# cart-breakout-r2.net
KiCad netlist of a schematic drawn in EAGLE
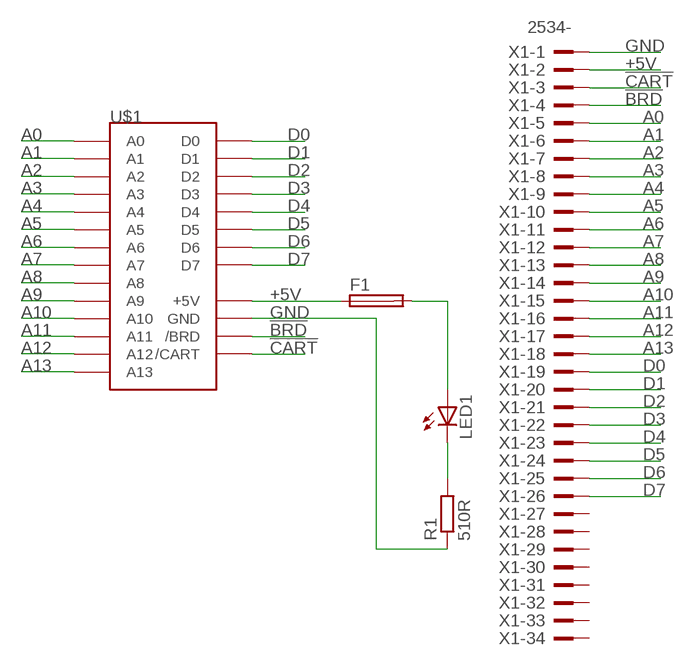
[diagram p0: schematic, sheet 1]

(export (version "E")
  (design (tool "Eeschema 10.0.6"))
  (components
    (comp (ref "F1")
      (value "TE5")
      (footprint "eagle-import:TE5")
      (libsource (lib "eagle-import") (part "TE5"))
    )
    (comp (ref "LED1")
      (value "LED5MM")
      (footprint "eagle-import:LED5MM")
      (libsource (lib "eagle-import") (part "LED5MM"))
    )
    (comp (ref "R1")
      (value "510R")
      (footprint "eagle-import:0204_7")
      (libsource (lib "eagle-import") (part "R-EU_0204/7"))
    )
    (comp (ref "U$1")
      (value "TVC-CART-EDGE+")
      (footprint "eagle-import:TVC-CART-EDGE")
      (libsource (lib "eagle-import") (part "TVC-CART-EDGE+"))
    )
    (comp (ref "X1")
      (value "2534-")
      (footprint "eagle-import:PAK100_2500-34")
      (libsource (lib "eagle-import") (part "2534-"))
    )
  )
  (nets
    (net (code "1") (name "/+5V") (class "Default")
      (node (ref "F1") (pin "1") (pinfunction "1_1") (pintype "passive"))
      (node (ref "F1") (pin "2") (pinfunction "2_2") (pintype "passive"))
      (node (ref "LED1") (pin "A") (pinfunction "A_A") (pintype "passive"))
      (node (ref "U$1") (pin "BTM10") (pinfunction "+5V_BTM10") (pintype "power_in"))
      (node (ref "U$1") (pin "BTM11") (pinfunction "+5V_BTM11") (pintype "power_in"))
      (node (ref "U$1") (pin "BTM12") (pinfunction "+5V_BTM12") (pintype "power_in"))
      (node (ref "U$1") (pin "BTM13") (pinfunction "+5V_BTM13") (pintype "power_in"))
      (node (ref "U$1") (pin "BTM14") (pinfunction "+5V_BTM14") (pintype "power_in"))
      (node (ref "U$1") (pin "BTM15") (pinfunction "+5V_BTM15") (pintype "power_in"))
      (node (ref "U$1") (pin "BTM16") (pinfunction "+5V_BTM16") (pintype "power_in"))
      (node (ref "U$1") (pin "BTM17") (pinfunction "+5V_BTM17") (pintype "power_in"))
      (node (ref "X1") (pin "2") (pinfunction "KL_2") (pintype "passive"))
    )
    (net (code "2") (name "/A0") (class "Default")
      (node (ref "U$1") (pin "TOP25") (pinfunction "A0_TOP25") (pintype "bidirectional"))
      (node (ref "X1") (pin "5") (pinfunction "KL_5") (pintype "passive"))
    )
    (net (code "3") (name "/A1") (class "Default")
      (node (ref "U$1") (pin "TOP2") (pinfunction "A1_TOP2") (pintype "bidirectional"))
      (node (ref "X1") (pin "6") (pinfunction "KL_6") (pintype "passive"))
    )
    (net (code "4") (name "/A2") (class "Default")
      (node (ref "U$1") (pin "TOP24") (pinfunction "A2_TOP24") (pintype "bidirectional"))
      (node (ref "X1") (pin "7") (pinfunction "KL_7") (pintype "passive"))
    )
    (net (code "5") (name "/A3") (class "Default")
      (node (ref "U$1") (pin "TOP1") (pinfunction "A3_TOP1") (pintype "bidirectional"))
      (node (ref "X1") (pin "8") (pinfunction "KL_8") (pintype "passive"))
    )
    (net (code "6") (name "/A4") (class "Default")
      (node (ref "U$1") (pin "TOP21") (pinfunction "A4_TOP21") (pintype "bidirectional"))
      (node (ref "X1") (pin "9") (pinfunction "KL_9") (pintype "passive"))
    )
    (net (code "7") (name "/A5") (class "Default")
      (node (ref "U$1") (pin "TOP14") (pinfunction "A5_TOP14") (pintype "bidirectional"))
      (node (ref "X1") (pin "10") (pinfunction "KL_10") (pintype "passive"))
    )
    (net (code "8") (name "/A6") (class "Default")
      (node (ref "U$1") (pin "TOP18") (pinfunction "A6_TOP18") (pintype "bidirectional"))
      (node (ref "X1") (pin "11") (pinfunction "KL_11") (pintype "passive"))
    )
    (net (code "9") (name "/A7") (class "Default")
      (node (ref "U$1") (pin "TOP17") (pinfunction "A7_TOP17") (pintype "bidirectional"))
      (node (ref "X1") (pin "12") (pinfunction "KL_12") (pintype "passive"))
    )
    (net (code "10") (name "/A8") (class "Default")
      (node (ref "U$1") (pin "TOP15") (pinfunction "A8_TOP15") (pintype "bidirectional"))
      (node (ref "X1") (pin "13") (pinfunction "KL_13") (pintype "passive"))
    )
    (net (code "11") (name "/A9") (class "Default")
      (node (ref "U$1") (pin "TOP19") (pinfunction "A9_TOP19") (pintype "bidirectional"))
      (node (ref "X1") (pin "14") (pinfunction "KL_14") (pintype "passive"))
    )
    (net (code "12") (name "/A10") (class "Default")
      (node (ref "U$1") (pin "TOP22") (pinfunction "A10_TOP22") (pintype "bidirectional"))
      (node (ref "X1") (pin "15") (pinfunction "KL_15") (pintype "passive"))
    )
    (net (code "13") (name "/A11") (class "Default")
      (node (ref "U$1") (pin "TOP20") (pinfunction "A11_TOP20") (pintype "bidirectional"))
      (node (ref "X1") (pin "16") (pinfunction "KL_16") (pintype "passive"))
    )
    (net (code "14") (name "/A12") (class "Default")
      (node (ref "U$1") (pin "TOP16") (pinfunction "A12_TOP16") (pintype "bidirectional"))
      (node (ref "X1") (pin "17") (pinfunction "KL_17") (pintype "passive"))
    )
    (net (code "15") (name "/A13") (class "Default")
      (node (ref "U$1") (pin "TOP23") (pinfunction "A13_TOP23") (pintype "bidirectional"))
      (node (ref "X1") (pin "18") (pinfunction "KL_18") (pintype "passive"))
    )
    (net (code "16") (name "/D0") (class "Default")
      (node (ref "U$1") (pin "TOP4") (pinfunction "D0_TOP4") (pintype "bidirectional"))
      (node (ref "X1") (pin "19") (pinfunction "KL_19") (pintype "passive"))
    )
    (net (code "17") (name "/D1") (class "Default")
      (node (ref "U$1") (pin "TOP5") (pinfunction "D1_TOP5") (pintype "bidirectional"))
      (node (ref "X1") (pin "20") (pinfunction "KL_20") (pintype "passive"))
    )
    (net (code "18") (name "/D2") (class "Default")
      (node (ref "U$1") (pin "TOP6") (pinfunction "D2_TOP6") (pintype "bidirectional"))
      (node (ref "X1") (pin "21") (pinfunction "KL_21") (pintype "passive"))
    )
    (net (code "19") (name "/D3") (class "Default")
      (node (ref "U$1") (pin "TOP7") (pinfunction "D3_TOP7") (pintype "bidirectional"))
      (node (ref "X1") (pin "22") (pinfunction "KL_22") (pintype "passive"))
    )
    (net (code "20") (name "/D4") (class "Default")
      (node (ref "U$1") (pin "TOP8") (pinfunction "D4_TOP8") (pintype "bidirectional"))
      (node (ref "X1") (pin "23") (pinfunction "KL_23") (pintype "passive"))
    )
    (net (code "21") (name "/D5") (class "Default")
      (node (ref "U$1") (pin "TOP9") (pinfunction "D5_TOP9") (pintype "bidirectional"))
      (node (ref "X1") (pin "24") (pinfunction "KL_24") (pintype "passive"))
    )
    (net (code "22") (name "/D6") (class "Default")
      (node (ref "U$1") (pin "TOP10") (pinfunction "D6_TOP10") (pintype "bidirectional"))
      (node (ref "X1") (pin "25") (pinfunction "KL_25") (pintype "passive"))
    )
    (net (code "23") (name "/D7") (class "Default")
      (node (ref "U$1") (pin "TOP3") (pinfunction "D7_TOP3") (pintype "bidirectional"))
      (node (ref "X1") (pin "26") (pinfunction "KL_26") (pintype "passive"))
    )
    (net (code "24") (name "/GND") (class "Default")
      (node (ref "R1") (pin "1") (pinfunction "1_1") (pintype "passive"))
      (node (ref "U$1") (pin "BTM1") (pinfunction "GND_BTM1") (pintype "power_in"))
      (node (ref "U$1") (pin "BTM2") (pinfunction "GND_BTM2") (pintype "power_in"))
      (node (ref "U$1") (pin "BTM3") (pinfunction "GND_BTM3") (pintype "power_in"))
      (node (ref "U$1") (pin "BTM4") (pinfunction "GND_BTM4") (pintype "power_in"))
      (node (ref "U$1") (pin "BTM5") (pinfunction "GND_BTM5") (pintype "power_in"))
      (node (ref "U$1") (pin "BTM6") (pinfunction "GND_BTM6") (pintype "power_in"))
      (node (ref "U$1") (pin "BTM7") (pinfunction "GND_BTM7") (pintype "power_in"))
      (node (ref "U$1") (pin "BTM8") (pinfunction "GND_BTM8") (pintype "power_in"))
      (node (ref "X1") (pin "1") (pinfunction "KL_1") (pintype "passive"))
    )
    (net (code "25") (name "/~{BRD}") (class "Default")
      (node (ref "U$1") (pin "BTM24") (pinfunction "/BRD_BTM24") (pintype "bidirectional"))
      (node (ref "X1") (pin "4") (pinfunction "KL_4") (pintype "passive"))
    )
    (net (code "26") (name "/~{CART}") (class "Default")
      (node (ref "U$1") (pin "BTM23") (pinfunction "/CART_BTM23") (pintype "bidirectional"))
      (node (ref "X1") (pin "3") (pinfunction "KL_3") (pintype "passive"))
    )
    (net (code "27") (name "Net-(LED1-C)") (class "Default")
      (node (ref "LED1") (pin "K") (pinfunction "C_K") (pintype "passive"))
      (node (ref "R1") (pin "2") (pinfunction "2_2") (pintype "passive"))
    )
    (net (code "28") (name "unconnected-(X1AA-KL-Pad33)") (class "Default")
      (node (ref "X1") (pin "33") (pinfunction "KL_33") (pintype "passive"))
    )
    (net (code "29") (name "unconnected-(X1AB-KL-Pad34)") (class "Default")
      (node (ref "X1") (pin "34") (pinfunction "KL_34") (pintype "passive"))
    )
    (net (code "30") (name "unconnected-(X1T-KL-Pad27)") (class "Default")
      (node (ref "X1") (pin "27") (pinfunction "KL_27") (pintype "passive"))
    )
    (net (code "31") (name "unconnected-(X1U-KL-Pad28)") (class "Default")
      (node (ref "X1") (pin "28") (pinfunction "KL_28") (pintype "passive"))
    )
    (net (code "32") (name "unconnected-(X1V-KL-Pad29)") (class "Default")
      (node (ref "X1") (pin "29") (pinfunction "KL_29") (pintype "passive"))
    )
    (net (code "33") (name "unconnected-(X1X-KL-Pad30)") (class "Default")
      (node (ref "X1") (pin "30") (pinfunction "KL_30") (pintype "passive"))
    )
    (net (code "34") (name "unconnected-(X1Y-KL-Pad31)") (class "Default")
      (node (ref "X1") (pin "31") (pinfunction "KL_31") (pintype "passive"))
    )
    (net (code "35") (name "unconnected-(X1Z-KL-Pad32)") (class "Default")
      (node (ref "X1") (pin "32") (pinfunction "KL_32") (pintype "passive"))
    )
  )
)
